# BMS_Schematic.net
KiCad netlist of a schematic drawn in EAGLE
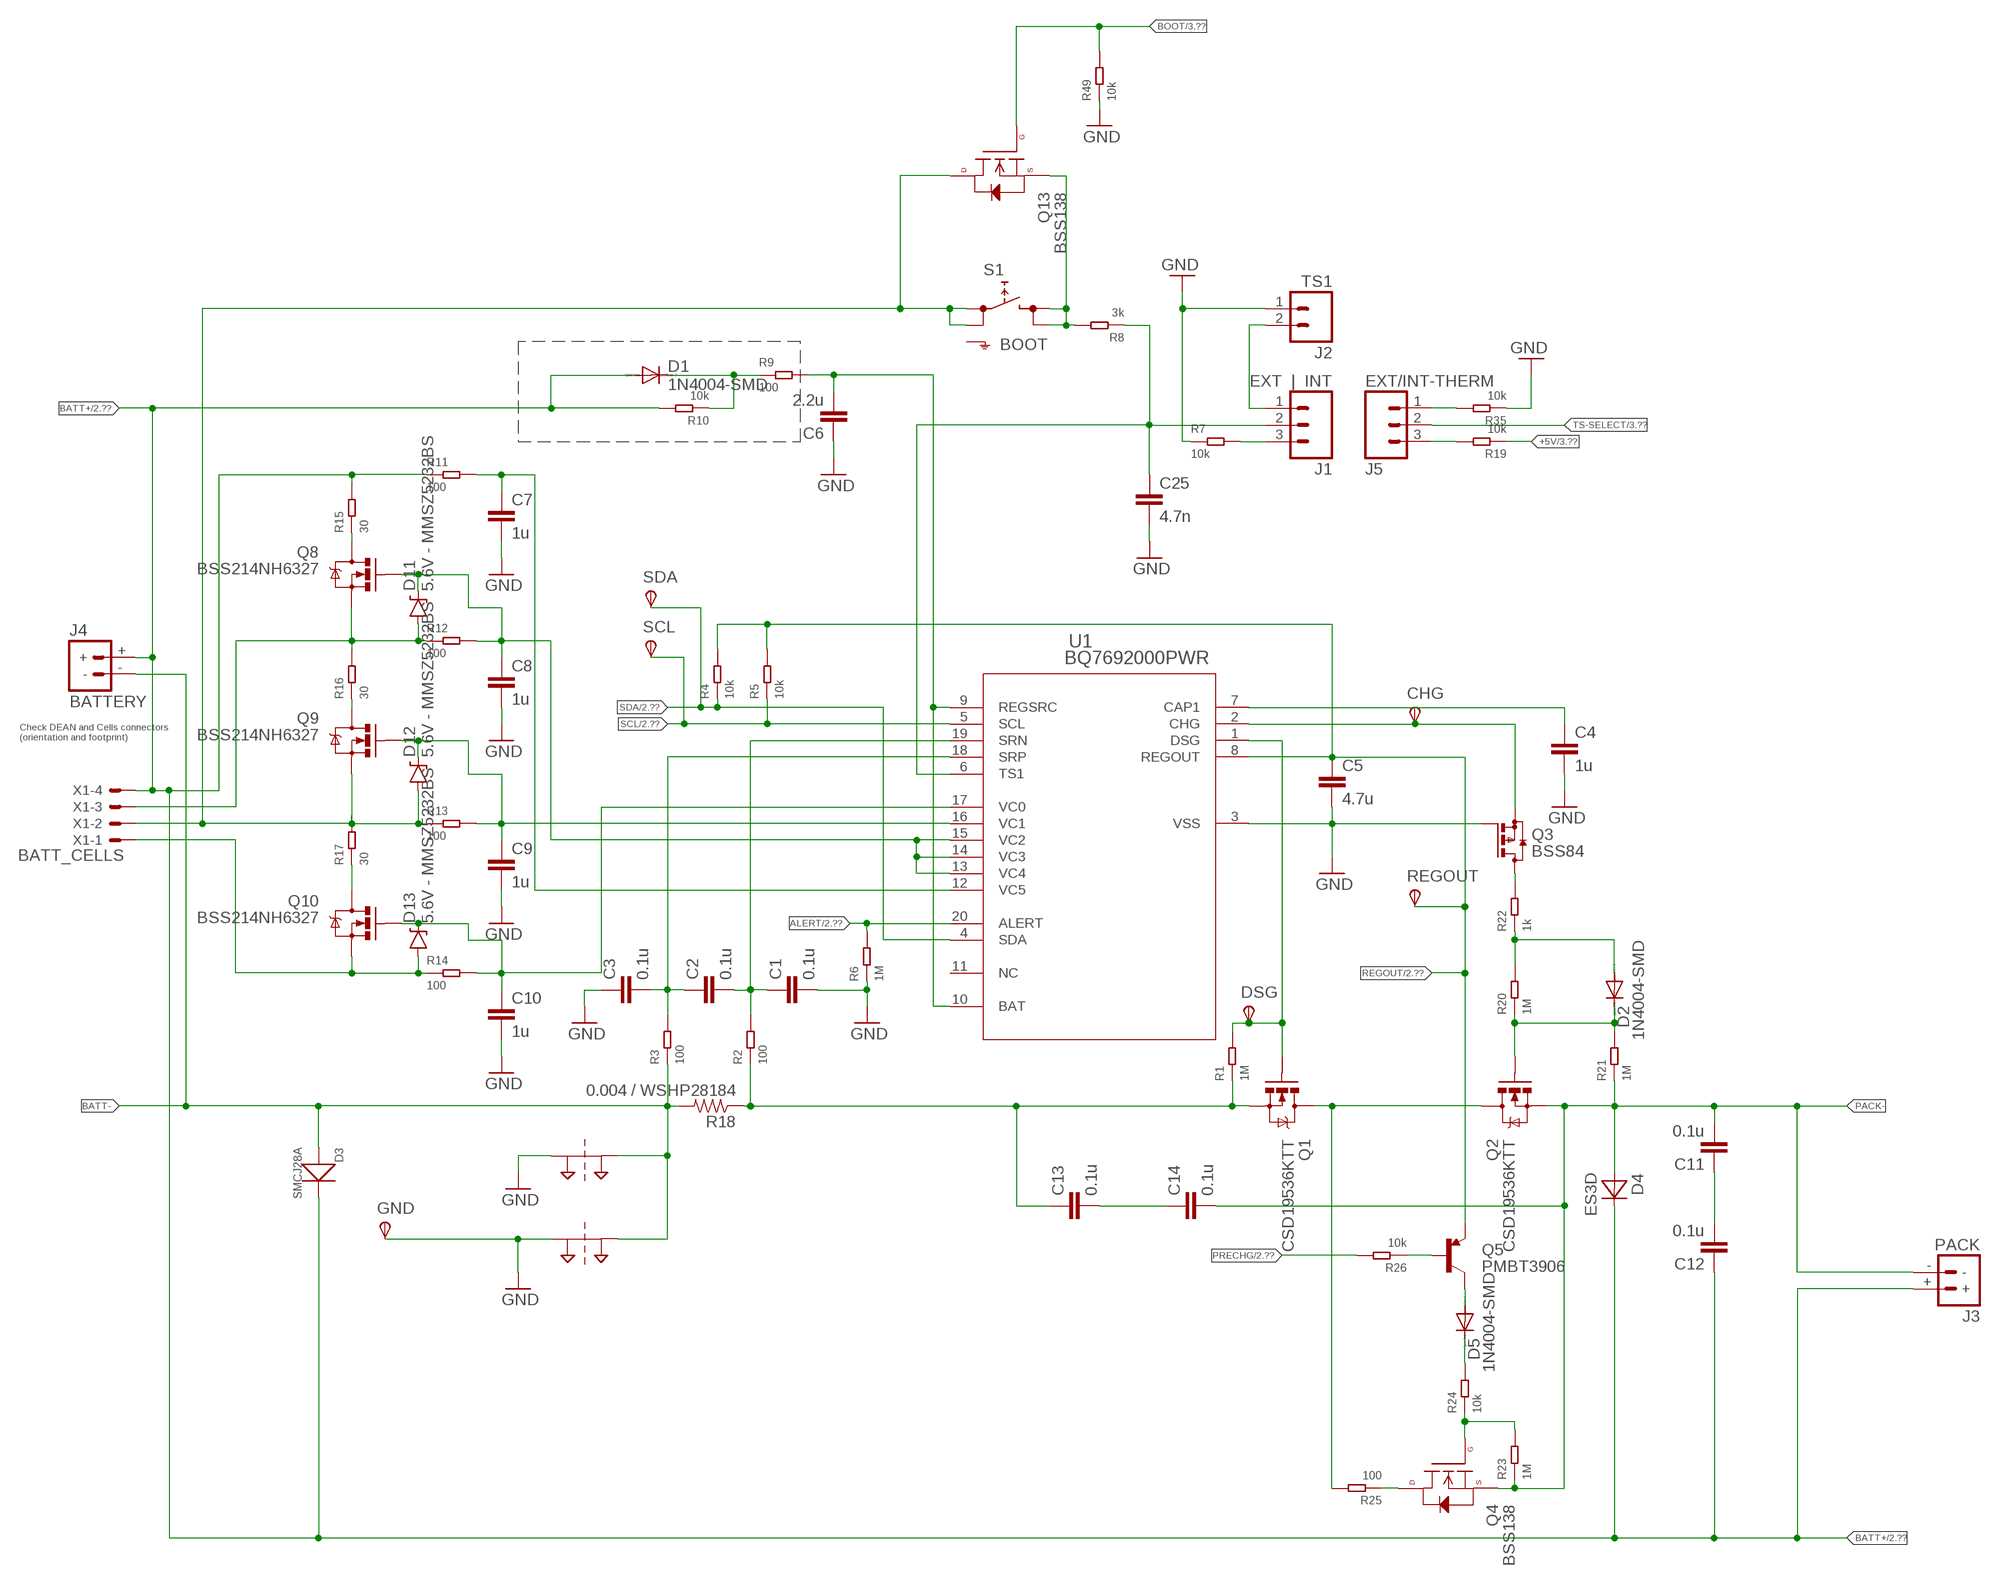
[diagram p0: schematic, sheet 1]
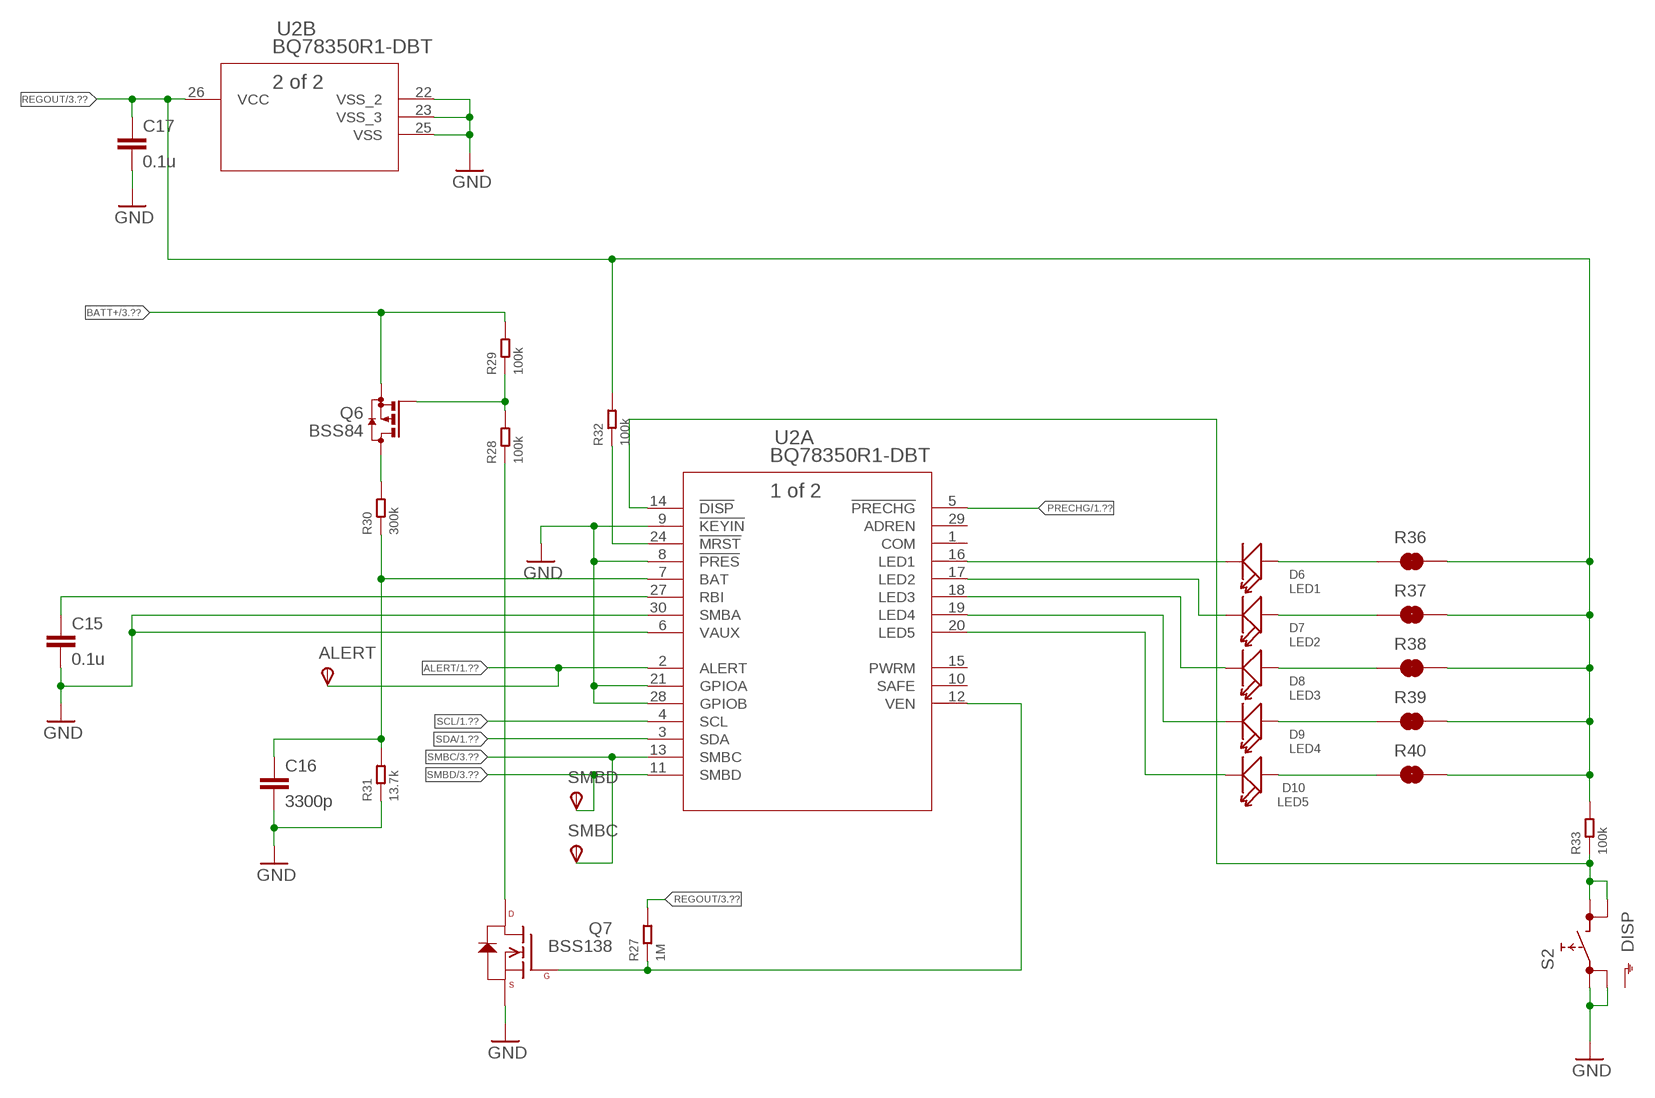
[diagram p1: schematic, sheet 2]
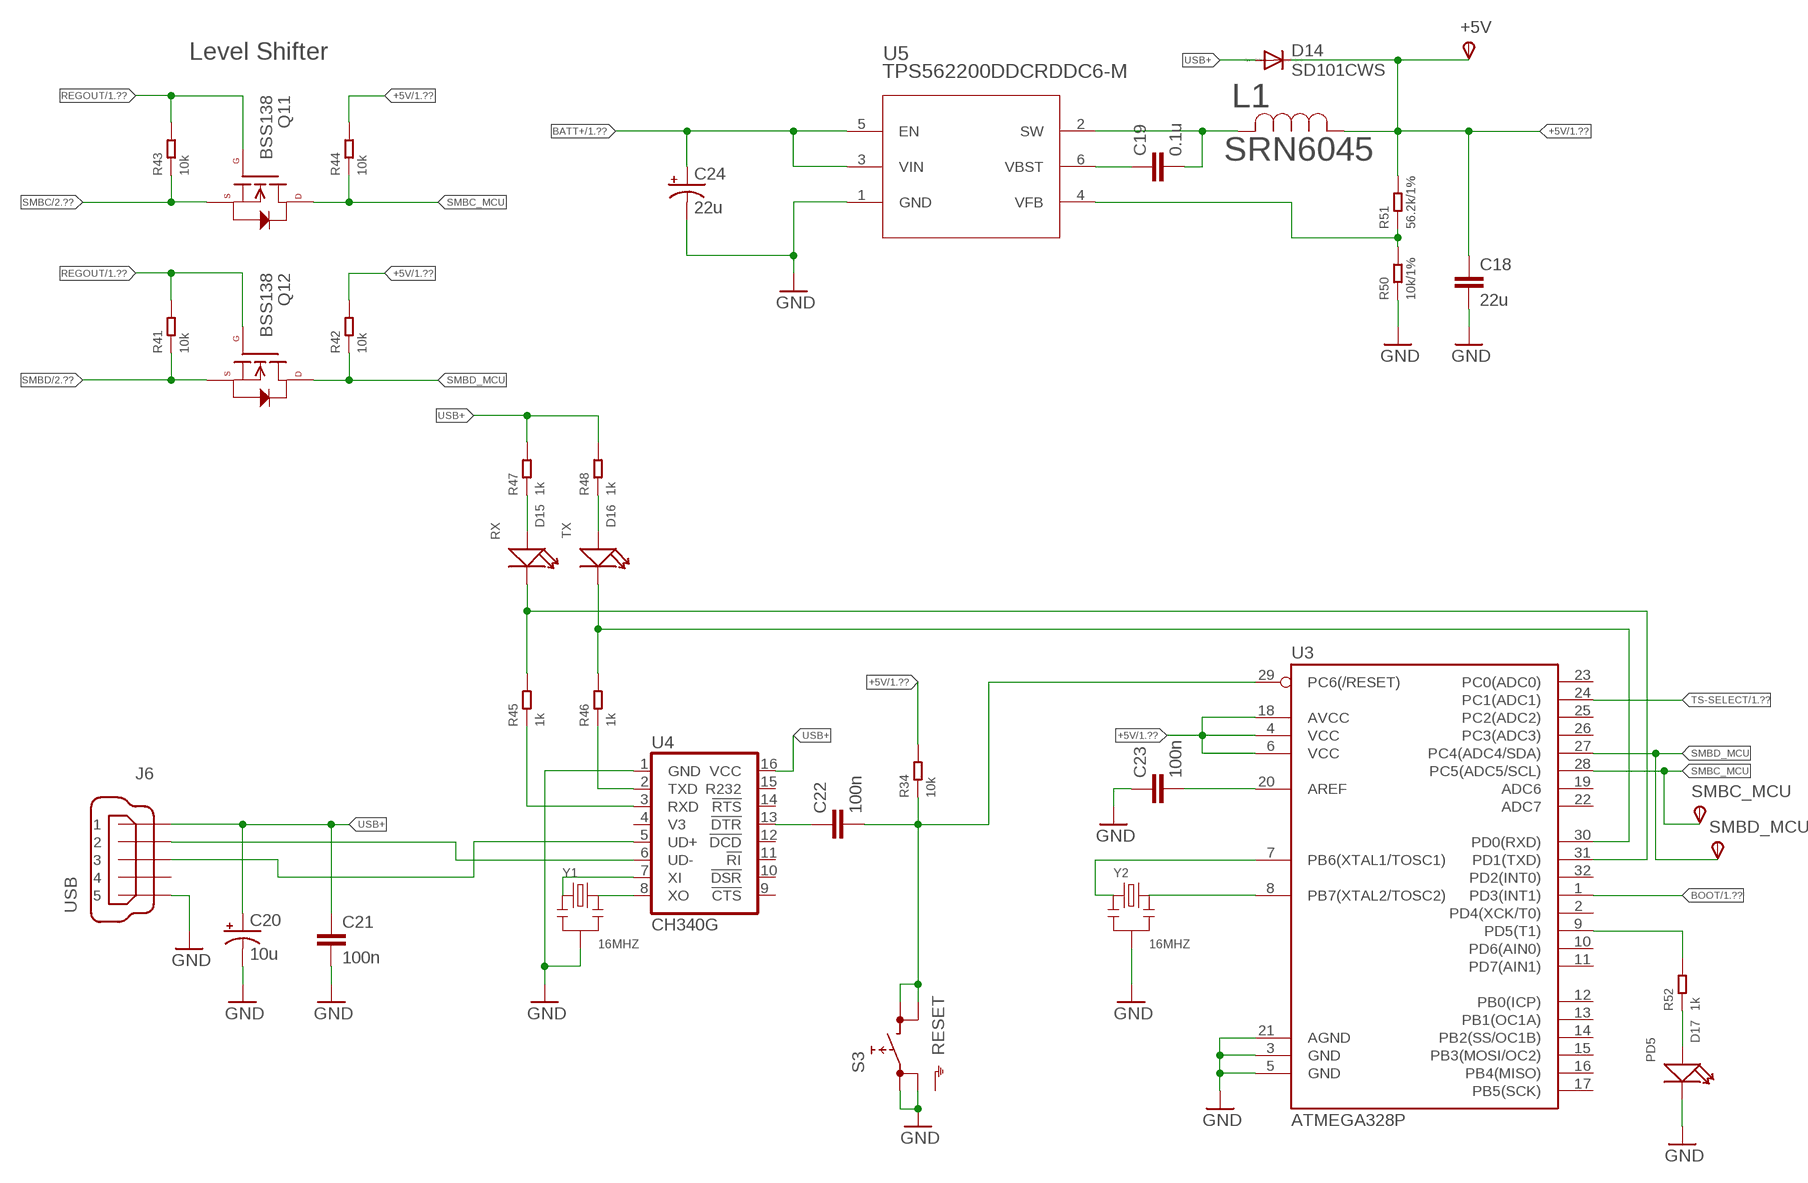
[diagram p2: schematic, sheet 3]

(export (version "E")
  (design (tool "Eeschema 10.0.6"))
  (components
    (comp (ref "C1")
      (value "0.1u")
      (footprint "eagle-import:0805")
      (libsource (lib "eagle-import") (part "CAP0805"))
    )
    (comp (ref "C2")
      (value "0.1u")
      (footprint "eagle-import:0805")
      (libsource (lib "eagle-import") (part "CAP0805"))
    )
    (comp (ref "C3")
      (value "0.1u")
      (footprint "eagle-import:0805")
      (libsource (lib "eagle-import") (part "CAP0805"))
    )
    (comp (ref "C4")
      (value "1u")
      (footprint "eagle-import:0805")
      (libsource (lib "eagle-import") (part "CAP0805"))
    )
    (comp (ref "C5")
      (value "4.7u")
      (footprint "eagle-import:0805")
      (libsource (lib "eagle-import") (part "CAP0805"))
    )
    (comp (ref "C6")
      (value "2.2u")
      (footprint "eagle-import:C1206")
      (libsource (lib "eagle-import") (part "C-EUC1206"))
    )
    (comp (ref "C7")
      (value "1u")
      (footprint "eagle-import:0805")
      (libsource (lib "eagle-import") (part "CAP0805"))
    )
    (comp (ref "C8")
      (value "1u")
      (footprint "eagle-import:0805")
      (libsource (lib "eagle-import") (part "CAP0805"))
    )
    (comp (ref "C9")
      (value "1u")
      (footprint "eagle-import:0805")
      (libsource (lib "eagle-import") (part "CAP0805"))
    )
    (comp (ref "C10")
      (value "1u")
      (footprint "eagle-import:0805")
      (libsource (lib "eagle-import") (part "CAP0805"))
    )
    (comp (ref "C11")
      (value "0.1u")
      (footprint "eagle-import:0805")
      (libsource (lib "eagle-import") (part "CAP0805"))
    )
    (comp (ref "C12")
      (value "0.1u")
      (footprint "eagle-import:0805")
      (libsource (lib "eagle-import") (part "CAP0805"))
    )
    (comp (ref "C13")
      (value "0.1u")
      (footprint "eagle-import:0805")
      (libsource (lib "eagle-import") (part "CAP0805"))
    )
    (comp (ref "C14")
      (value "0.1u")
      (footprint "eagle-import:0805")
      (libsource (lib "eagle-import") (part "CAP0805"))
    )
    (comp (ref "C25")
      (value "4.7n")
      (footprint "eagle-import:0805")
      (libsource (lib "eagle-import") (part "CAP0805"))
    )
    (comp (ref "CHG")
      (value "TPSB2,54")
      (footprint "eagle-import:B2,54")
      (libsource (lib "eagle-import") (part "TPSB2,54"))
    )
    (comp (ref "D1")
      (value "1N4004-SMD")
      (footprint "eagle-import:DO-214")
      (libsource (lib "eagle-import") (part "1N4004-SMD"))
    )
    (comp (ref "D2")
      (value "1N4004-SMD")
      (footprint "eagle-import:DO-214")
      (libsource (lib "eagle-import") (part "1N4004-SMD"))
    )
    (comp (ref "D3")
      (value "SMCJ28A")
      (footprint "eagle-import:DO-214AB")
      (fields (field (name "MPN") "SS34-E3/57T"))
      (libsource (lib "eagle-import") (part "SMD-DIODE-SCHOTTKY-40V-3A(DO-214AB)"))
    )
    (comp (ref "D4")
      (value "ES3D")
      (footprint "eagle-import:SMC")
      (libsource (lib "eagle-import") (part "ES3D"))
    )
    (comp (ref "D5")
      (value "1N4004-SMD")
      (footprint "eagle-import:DO-214")
      (libsource (lib "eagle-import") (part "1N4004-SMD"))
    )
    (comp (ref "D11")
      (value "5.6V - MMSZ5232BS")
      (footprint "eagle-import:SOD-323")
      (libsource (lib "eagle-import") (part "DIODE-ZENER5.6V"))
    )
    (comp (ref "D12")
      (value "5.6V - MMSZ5232BS")
      (footprint "eagle-import:SOD-323")
      (libsource (lib "eagle-import") (part "DIODE-ZENER5.6V"))
    )
    (comp (ref "D13")
      (value "5.6V - MMSZ5232BS")
      (footprint "eagle-import:SOD-323")
      (libsource (lib "eagle-import") (part "DIODE-ZENER5.6V"))
    )
    (comp (ref "DSG")
      (value "TPSB2,54")
      (footprint "eagle-import:B2,54")
      (libsource (lib "eagle-import") (part "TPSB2,54"))
    )
    (comp (ref "GND")
      (value "GND")
      (footprint "eagle-import:P1-17")
      (fields (field (name "SPICEPREFIX") "X"))
      (libsource (lib "eagle-import") (part "TPSPAD1-17"))
    )
    (comp (ref "J1")
      (value "EXT | INT")
      (footprint "eagle-import:1X03")
      (libsource (lib "eagle-import") (part "M03PTH"))
    )
    (comp (ref "J2")
      (value "TS1")
      (footprint "eagle-import:1X02")
      (libsource (lib "eagle-import") (part "M02PTH"))
    )
    (comp (ref "J3")
      (value "PACK")
      (footprint "eagle-import:DEANS")
      (libsource (lib "eagle-import") (part "BATTERY_CONNDEANS"))
    )
    (comp (ref "J4")
      (value "BATTERY")
      (footprint "eagle-import:DEANS")
      (libsource (lib "eagle-import") (part "BATTERY_CONNDEANS"))
    )
    (comp (ref "J5")
      (value "EXT/INT-THERM")
      (footprint "eagle-import:1X03")
      (libsource (lib "eagle-import") (part "M03PTH"))
    )
    (comp (ref "PT1")
      (value "2PT_GND_TIE")
      (footprint "eagle-import:2PT_GND_TIE")
      (libsource (lib "eagle-import") (part "2PT_GND_TIE"))
    )
    (comp (ref "PT2")
      (value "2PT_GND_TIE")
      (footprint "eagle-import:2PT_GND_TIE")
      (libsource (lib "eagle-import") (part "2PT_GND_TIE"))
    )
    (comp (ref "Q1")
      (value "CSD19536KTT")
      (footprint "eagle-import:TO-263_D2PAK")
      (libsource (lib "eagle-import") (part "MOSFET-NCHANNELPSMN7R0"))
    )
    (comp (ref "Q2")
      (value "CSD19536KTT")
      (footprint "eagle-import:TO-263_D2PAK")
      (libsource (lib "eagle-import") (part "MOSFET-NCHANNELPSMN7R0"))
    )
    (comp (ref "Q3")
      (value "BSS84")
      (footprint "eagle-import:SOT23")
      (libsource (lib "eagle-import") (part "BSS84"))
    )
    (comp (ref "Q4")
      (value "BSS138")
      (footprint "eagle-import:SOT23-3")
      (libsource (lib "eagle-import") (part "N-CHANNEL-MOSFET-BSS138"))
    )
    (comp (ref "Q5")
      (value "PMBT3906")
      (footprint "eagle-import:SOT23-3")
      (libsource (lib "eagle-import") (part "TRANSISTOR_PNPPMBT3906"))
    )
    (comp (ref "Q8")
      (value "BSS214NH6327")
      (footprint "eagle-import:SOT23-3")
      (libsource (lib "eagle-import") (part "MOSFET-NCHANNELBSS138"))
    )
    (comp (ref "Q9")
      (value "BSS214NH6327")
      (footprint "eagle-import:SOT23-3")
      (libsource (lib "eagle-import") (part "MOSFET-NCHANNELBSS138"))
    )
    (comp (ref "Q10")
      (value "BSS214NH6327")
      (footprint "eagle-import:SOT23-3")
      (libsource (lib "eagle-import") (part "MOSFET-NCHANNELBSS138"))
    )
    (comp (ref "Q13")
      (value "BSS138")
      (footprint "eagle-import:SOT23-3")
      (libsource (lib "eagle-import") (part "N-CHANNEL-MOSFET-BSS138"))
    )
    (comp (ref "R1")
      (value "1M")
      (footprint "eagle-import:R0805")
      (libsource (lib "eagle-import") (part "RES-0805"))
    )
    (comp (ref "R2")
      (value "100")
      (footprint "eagle-import:R0805")
      (libsource (lib "eagle-import") (part "RES-0805"))
    )
    (comp (ref "R3")
      (value "100")
      (footprint "eagle-import:R0805")
      (libsource (lib "eagle-import") (part "RES-0805"))
    )
    (comp (ref "R4")
      (value "10k")
      (footprint "eagle-import:R0805")
      (libsource (lib "eagle-import") (part "RES-0805"))
    )
    (comp (ref "R5")
      (value "10k")
      (footprint "eagle-import:R0805")
      (libsource (lib "eagle-import") (part "RES-0805"))
    )
    (comp (ref "R6")
      (value "1M")
      (footprint "eagle-import:R0805")
      (libsource (lib "eagle-import") (part "RES-0805"))
    )
    (comp (ref "R7")
      (value "10k")
      (footprint "eagle-import:R0805")
      (libsource (lib "eagle-import") (part "RES-0805"))
    )
    (comp (ref "R8")
      (value "3k")
      (footprint "eagle-import:R0805")
      (libsource (lib "eagle-import") (part "RES-0805"))
    )
    (comp (ref "R9")
      (value "100")
      (footprint "eagle-import:R0805")
      (libsource (lib "eagle-import") (part "RES-0805"))
    )
    (comp (ref "R10")
      (value "10k")
      (footprint "eagle-import:R0805")
      (libsource (lib "eagle-import") (part "RES-0805"))
    )
    (comp (ref "R11")
      (value "100")
      (footprint "eagle-import:R0805")
      (libsource (lib "eagle-import") (part "RES-0805"))
    )
    (comp (ref "R12")
      (value "100")
      (footprint "eagle-import:R0805")
      (libsource (lib "eagle-import") (part "RES-0805"))
    )
    (comp (ref "R13")
      (value "100")
      (footprint "eagle-import:R0805")
      (libsource (lib "eagle-import") (part "RES-0805"))
    )
    (comp (ref "R14")
      (value "100")
      (footprint "eagle-import:R0805")
      (libsource (lib "eagle-import") (part "RES-0805"))
    )
    (comp (ref "R15")
      (value "30")
      (footprint "eagle-import:R2512")
      (libsource (lib "eagle-import") (part "RES-2512"))
    )
    (comp (ref "R16")
      (value "30")
      (footprint "eagle-import:R2512")
      (libsource (lib "eagle-import") (part "RES-2512"))
    )
    (comp (ref "R17")
      (value "30")
      (footprint "eagle-import:R2512")
      (libsource (lib "eagle-import") (part "RES-2512"))
    )
    (comp (ref "R18")
      (value "0.004 / WSHP28184")
      (footprint "eagle-import:2512")
      (libsource (lib "eagle-import") (part "0.001OHM-3W-1%(2512)3W/1%"))
    )
    (comp (ref "R19")
      (value "10k")
      (footprint "eagle-import:R0805")
      (libsource (lib "eagle-import") (part "RES-0805"))
    )
    (comp (ref "R20")
      (value "1M")
      (footprint "eagle-import:R0805")
      (libsource (lib "eagle-import") (part "RES-0805"))
    )
    (comp (ref "R21")
      (value "1M")
      (footprint "eagle-import:R0805")
      (libsource (lib "eagle-import") (part "RES-0805"))
    )
    (comp (ref "R22")
      (value "1k")
      (footprint "eagle-import:R0805")
      (libsource (lib "eagle-import") (part "RES-0805"))
    )
    (comp (ref "R23")
      (value "1M")
      (footprint "eagle-import:R0805")
      (libsource (lib "eagle-import") (part "RES-0805"))
    )
    (comp (ref "R24")
      (value "10k")
      (footprint "eagle-import:R0805")
      (libsource (lib "eagle-import") (part "RES-0805"))
    )
    (comp (ref "R25")
      (value "100")
      (footprint "eagle-import:R2512")
      (libsource (lib "eagle-import") (part "RES-2512"))
    )
    (comp (ref "R26")
      (value "10k")
      (footprint "eagle-import:R0805")
      (libsource (lib "eagle-import") (part "RES-0805"))
    )
    (comp (ref "R35")
      (value "10k")
      (footprint "eagle-import:R0805")
      (libsource (lib "eagle-import") (part "RES-0805"))
    )
    (comp (ref "R49")
      (value "10k")
      (footprint "eagle-import:R0805")
      (libsource (lib "eagle-import") (part "RES-0805"))
    )
    (comp (ref "REGOUT")
      (value "TPSB2,54")
      (footprint "eagle-import:B2,54")
      (libsource (lib "eagle-import") (part "TPSB2,54"))
    )
    (comp (ref "S1")
      (value "BOOT")
      (footprint "eagle-import:SKHMPXE010")
      (libsource (lib "eagle-import") (part "SKHMPE010S"))
    )
    (comp (ref "SCL")
      (value "TPSB2,54")
      (footprint "eagle-import:B2,54")
      (libsource (lib "eagle-import") (part "TPSB2,54"))
    )
    (comp (ref "SDA")
      (value "TPSB2,54")
      (footprint "eagle-import:B2,54")
      (libsource (lib "eagle-import") (part "TPSB2,54"))
    )
    (comp (ref "U1")
      (value "BQ7692000PWR")
      (footprint "eagle-import:PW20")
      (fields (field (name "MANUFACTURER_PART_NUMBER") "BQ7692006PWR"))
      (libsource (lib "eagle-import") (part "BQ7692006PWR"))
    )
    (comp (ref "X1")
      (value "BATT_CELLS")
      (footprint "eagle-import:70543-04")
      (libsource (lib "eagle-import") (part "C-GRID-04-70543"))
    )
    (comp (ref "ALERT")
      (value "TPSB2,54")
      (footprint "eagle-import:B2,54")
      (libsource (lib "eagle-import") (part "TPSB2,54"))
    )
    (comp (ref "C15")
      (value "0.1u")
      (footprint "eagle-import:0805")
      (libsource (lib "eagle-import") (part "CAP0805"))
    )
    (comp (ref "C16")
      (value "3300p")
      (footprint "eagle-import:0805")
      (libsource (lib "eagle-import") (part "CAP0805"))
    )
    (comp (ref "C17")
      (value "0.1u")
      (footprint "eagle-import:0805")
      (libsource (lib "eagle-import") (part "CAP0805"))
    )
    (comp (ref "D6")
      (value "LED1")
      (footprint "eagle-import:LED-0805")
      (fields (field (name "MPN") "17-215SYGC/S530-E2/TR8"))
      (libsource (lib "eagle-import") (part "SMD-LED-CLEAR-GREEN(0805)"))
    )
    (comp (ref "D7")
      (value "LED2")
      (footprint "eagle-import:LED-0805")
      (fields (field (name "MPN") "17-215SYGC/S530-E2/TR8"))
      (libsource (lib "eagle-import") (part "SMD-LED-CLEAR-GREEN(0805)"))
    )
    (comp (ref "D8")
      (value "LED3")
      (footprint "eagle-import:LED-0805")
      (fields (field (name "MPN") "17-215SYGC/S530-E2/TR8"))
      (libsource (lib "eagle-import") (part "SMD-LED-CLEAR-GREEN(0805)"))
    )
    (comp (ref "D9")
      (value "LED4")
      (footprint "eagle-import:LED-0805")
      (fields (field (name "MPN") "17-215SYGC/S530-E2/TR8"))
      (libsource (lib "eagle-import") (part "SMD-LED-CLEAR-GREEN(0805)"))
    )
    (comp (ref "D10")
      (value "LED5")
      (footprint "eagle-import:LED-0805")
      (fields (field (name "MPN") "17-215SURC/S530-A2/TR8"))
      (libsource (lib "eagle-import") (part "SMD-LED-CLEAR-RED(0805)"))
    )
    (comp (ref "Q6")
      (value "BSS84")
      (footprint "eagle-import:SOT23")
      (libsource (lib "eagle-import") (part "BSS84"))
    )
    (comp (ref "Q7")
      (value "BSS138")
      (footprint "eagle-import:SOT23-3")
      (libsource (lib "eagle-import") (part "N-CHANNEL-MOSFET-BSS138"))
    )
    (comp (ref "R27")
      (value "1M")
      (footprint "eagle-import:R0805")
      (libsource (lib "eagle-import") (part "RES-0805"))
    )
    (comp (ref "R28")
      (value "100k")
      (footprint "eagle-import:R0805")
      (libsource (lib "eagle-import") (part "RES-0805"))
    )
    (comp (ref "R29")
      (value "100k")
      (footprint "eagle-import:R0805")
      (libsource (lib "eagle-import") (part "RES-0805"))
    )
    (comp (ref "R30")
      (value "300k")
      (footprint "eagle-import:R0805")
      (libsource (lib "eagle-import") (part "RES-0805"))
    )
    (comp (ref "R31")
      (value "13.7k")
      (footprint "eagle-import:R0805")
      (libsource (lib "eagle-import") (part "RES-0805"))
    )
    (comp (ref "R32")
      (value "100k")
      (footprint "eagle-import:R0805")
      (libsource (lib "eagle-import") (part "RES-0805"))
    )
    (comp (ref "R33")
      (value "100k")
      (footprint "eagle-import:R0805")
      (libsource (lib "eagle-import") (part "RES-0805"))
    )
    (comp (ref "R36")
      (value "JUMPER-NC-0805")
      (footprint "eagle-import:R0805")
      (libsource (lib "eagle-import") (part "JUMPER-NC-0805"))
    )
    (comp (ref "R37")
      (value "JUMPER-NC-0805")
      (footprint "eagle-import:R0805")
      (libsource (lib "eagle-import") (part "JUMPER-NC-0805"))
    )
    (comp (ref "R38")
      (value "JUMPER-NC-0805")
      (footprint "eagle-import:R0805")
      (libsource (lib "eagle-import") (part "JUMPER-NC-0805"))
    )
    (comp (ref "R39")
      (value "JUMPER-NC-0805")
      (footprint "eagle-import:R0805")
      (libsource (lib "eagle-import") (part "JUMPER-NC-0805"))
    )
    (comp (ref "R40")
      (value "JUMPER-NC-0805")
      (footprint "eagle-import:R0805")
      (libsource (lib "eagle-import") (part "JUMPER-NC-0805"))
    )
    (comp (ref "S2")
      (value "DISP")
      (footprint "eagle-import:SKHMPXE010")
      (libsource (lib "eagle-import") (part "SKHMPE010S"))
    )
    (comp (ref "SMBC")
      (value "TPSB2,54")
      (footprint "eagle-import:B2,54")
      (libsource (lib "eagle-import") (part "TPSB2,54"))
    )
    (comp (ref "SMBD")
      (value "TPSB2,54")
      (footprint "eagle-import:B2,54")
      (libsource (lib "eagle-import") (part "TPSB2,54"))
    )
    (comp (ref "U2")
      (value "BQ78350R1-DBT")
      (footprint "eagle-import:DBT30")
      (fields (field (name "MANUFACTURER_PART_NUMBER") "BQ78350DBT"))
      (libsource (lib "eagle-import") (part "BQ78350R1-DBT"))
    )
    (comp (ref "+5V")
      (value "TPSB2,54")
      (footprint "eagle-import:B2,54")
      (libsource (lib "eagle-import") (part "TPSB2,54"))
    )
    (comp (ref "C18")
      (value "22u")
      (footprint "eagle-import:0805")
      (libsource (lib "eagle-import") (part "CAP0805"))
    )
    (comp (ref "C19")
      (value "0.1u")
      (footprint "eagle-import:0805")
      (libsource (lib "eagle-import") (part "CAP0805"))
    )
    (comp (ref "C20")
      (value "10u")
      (footprint "eagle-import:EIA3216-KIT")
      (libsource (lib "eagle-import") (part "CAP_POL1206-KIT"))
    )
    (comp (ref "C21")
      (value "100n")
      (footprint "eagle-import:0603-CAP")
      (libsource (lib "eagle-import") (part "CAP0603-CAP"))
    )
    (comp (ref "C22")
      (value "100n")
      (footprint "eagle-import:0603-CAP")
      (libsource (lib "eagle-import") (part "CAP0603-CAP"))
    )
    (comp (ref "C23")
      (value "100n")
      (footprint "eagle-import:0603-CAP")
      (libsource (lib "eagle-import") (part "CAP0603-CAP"))
    )
    (comp (ref "C24")
      (value "22u")
      (footprint "eagle-import:PANASONIC_C")
      (libsource (lib "eagle-import") (part "CAP_POLC"))
    )
    (comp (ref "D14")
      (value "SD101CWS")
      (footprint "eagle-import:SOD323-W")
      (libsource (lib "eagle-import") (part "DIODE-SOD323-W"))
    )
    (comp (ref "D15")
      (value "RX")
      (footprint "eagle-import:LED-0805")
      (fields (field (name "MPN") "17-215SYGC/S530-E2/TR8"))
      (libsource (lib "eagle-import") (part "SMD-LED-CLEAR-GREEN(0805)"))
    )
    (comp (ref "D16")
      (value "TX")
      (footprint "eagle-import:LED-0805")
      (fields (field (name "MPN") "17-215SYGC/S530-E2/TR8"))
      (libsource (lib "eagle-import") (part "SMD-LED-CLEAR-GREEN(0805)"))
    )
    (comp (ref "D17")
      (value "PD5")
      (footprint "eagle-import:LED-0805")
      (fields (field (name "MPN") "17-215SYGC/S530-E2/TR8"))
      (libsource (lib "eagle-import") (part "SMD-LED-CLEAR-GREEN(0805)"))
    )
    (comp (ref "J6")
      (value "USB")
      (footprint "eagle-import:USB-MINI-B_2")
      (libsource (lib "eagle-import") (part "MINI-USB-ARDUINO-NANO"))
    )
    (comp (ref "L1")
      (value "SRN6045")
      (footprint "eagle-import:IND_BOURNS_SRN6045")
      (libsource (lib "eagle-import") (part "BOURNS_SRN6045"))
    )
    (comp (ref "Q11")
      (value "BSS138")
      (footprint "eagle-import:SOT23-3")
      (libsource (lib "eagle-import") (part "N-CHANNEL-MOSFET-BSS138"))
    )
    (comp (ref "Q12")
      (value "BSS138")
      (footprint "eagle-import:SOT23-3")
      (libsource (lib "eagle-import") (part "N-CHANNEL-MOSFET-BSS138"))
    )
    (comp (ref "R34")
      (value "10k")
      (footprint "eagle-import:R0805")
      (libsource (lib "eagle-import") (part "RES-0805"))
    )
    (comp (ref "R41")
      (value "10k")
      (footprint "eagle-import:R0805")
      (libsource (lib "eagle-import") (part "RES-0805"))
    )
    (comp (ref "R42")
      (value "10k")
      (footprint "eagle-import:R0805")
      (libsource (lib "eagle-import") (part "RES-0805"))
    )
    (comp (ref "R43")
      (value "10k")
      (footprint "eagle-import:R0805")
      (libsource (lib "eagle-import") (part "RES-0805"))
    )
    (comp (ref "R44")
      (value "10k")
      (footprint "eagle-import:R0805")
      (libsource (lib "eagle-import") (part "RES-0805"))
    )
    (comp (ref "R45")
      (value "1k")
      (footprint "eagle-import:R0805")
      (libsource (lib "eagle-import") (part "RES-0805"))
    )
    (comp (ref "R46")
      (value "1k")
      (footprint "eagle-import:R0805")
      (libsource (lib "eagle-import") (part "RES-0805"))
    )
    (comp (ref "R47")
      (value "1k")
      (footprint "eagle-import:R0805")
      (libsource (lib "eagle-import") (part "RES-0805"))
    )
    (comp (ref "R48")
      (value "1k")
      (footprint "eagle-import:R0805")
      (libsource (lib "eagle-import") (part "RES-0805"))
    )
    (comp (ref "R50")
      (value "10k/1%")
      (footprint "eagle-import:R0805")
      (libsource (lib "eagle-import") (part "RES-0805"))
    )
    (comp (ref "R51")
      (value "56.2k/1%")
      (footprint "eagle-import:R0805")
      (libsource (lib "eagle-import") (part "RES-0805"))
    )
    (comp (ref "R52")
      (value "1k")
      (footprint "eagle-import:R0805")
      (libsource (lib "eagle-import") (part "RES-0805"))
    )
    (comp (ref "S3")
      (value "RESET")
      (footprint "eagle-import:SKHMPXE010")
      (libsource (lib "eagle-import") (part "SKHMPE010S"))
    )
    (comp (ref "SMBC_MCU")
      (value "TPSB2,54")
      (footprint "eagle-import:B2,54")
      (libsource (lib "eagle-import") (part "TPSB2,54"))
    )
    (comp (ref "SMBD_MCU")
      (value "TPSB2,54")
      (footprint "eagle-import:B2,54")
      (libsource (lib "eagle-import") (part "TPSB2,54"))
    )
    (comp (ref "U3")
      (value "ATMEGA328P")
      (footprint "eagle-import:TQFP32-08")
      (libsource (lib "eagle-import") (part "ATMEGA328P_TQFP"))
    )
    (comp (ref "U4")
      (value "CH340G")
      (footprint "eagle-import:SO016")
      (libsource (lib "eagle-import") (part "CH340GSMD"))
    )
    (comp (ref "U5")
      (value "TPS562200DDCRDDC6-M")
      (footprint "eagle-import:DDC6-M")
      (fields (field (name "MANUFACTURER_PART_NUMBER") "TPS562200DDCR"))
      (libsource (lib "eagle-import") (part "TPS562200DDCRDDC6-M"))
    )
    (comp (ref "Y1")
      (value "16MHZ")
      (footprint "eagle-import:X3-SMD-3.6X1.3X0.8MM")
      (fields (field (name "MPN") "CSTCE16M0V53-R0"))
      (libsource (lib "eagle-import") (part "SMD-RESONATOR-16MHZ-15PF-0.5%-40R(3P-3.2X1.3MM)"))
    )
    (comp (ref "Y2")
      (value "16MHZ")
      (footprint "eagle-import:X3-SMD-3.6X1.3X0.8MM")
      (fields (field (name "MPN") "CSTCE16M0V53-R0"))
      (libsource (lib "eagle-import") (part "SMD-RESONATOR-16MHZ-15PF-0.5%-40R(3P-3.2X1.3MM)"))
    )
  )
  (nets
    (net (code "1") (name "+5V") (class "Default")
      (node (ref "+5V") (pin "TP") (pinfunction "PP_TP") (pintype "input"))
      (node (ref "C18") (pin "1") (pinfunction "1_1") (pintype "passive"))
      (node (ref "D14") (pin "C") (pinfunction "C_C") (pintype "passive"))
      (node (ref "L1") (pin "1") (pinfunction "1_1") (pintype "passive"))
      (node (ref "R19") (pin "1") (pinfunction "1_1") (pintype "passive"))
      (node (ref "R34") (pin "2") (pinfunction "2_2") (pintype "passive"))
      (node (ref "R42") (pin "2") (pinfunction "2_2") (pintype "passive"))
      (node (ref "R44") (pin "2") (pinfunction "2_2") (pintype "passive"))
      (node (ref "R51") (pin "2") (pinfunction "2_2") (pintype "passive"))
      (node (ref "U3") (pin "18") (pinfunction "AVCC_18") (pintype "bidirectional"))
      (node (ref "U3") (pin "4") (pinfunction "VCC_4") (pintype "bidirectional"))
      (node (ref "U3") (pin "6") (pinfunction "VCC_6") (pintype "bidirectional"))
    )
    (net (code "2") (name "ALERT") (class "Default")
      (node (ref "ALERT") (pin "TP") (pinfunction "PP_TP") (pintype "input"))
      (node (ref "R6") (pin "2") (pinfunction "2_2") (pintype "passive"))
      (node (ref "U1") (pin "20") (pinfunction "ALERT_20") (pintype "bidirectional"))
      (node (ref "U2") (pin "2") (pinfunction "ALERT_2") (pintype "bidirectional"))
    )
    (net (code "3") (name "BATT+") (class "Default")
      (node (ref "C12") (pin "1") (pinfunction "1_1") (pintype "passive"))
      (node (ref "C24") (pin "+") (pinfunction "+_+") (pintype "passive"))
      (node (ref "D1") (pin "A") (pinfunction "A_A") (pintype "passive"))
      (node (ref "D3") (pin "2") (pinfunction "-_2") (pintype "passive"))
      (node (ref "D4") (pin "C") (pinfunction "C_C") (pintype "passive"))
      (node (ref "J3") (pin "+") (pinfunction "+_+") (pintype "passive"))
      (node (ref "J4") (pin "+") (pinfunction "+_+") (pintype "passive"))
      (node (ref "Q6") (pin "2") (pinfunction "S_2") (pintype "passive"))
      (node (ref "R10") (pin "2") (pinfunction "2_2") (pintype "passive"))
      (node (ref "R11") (pin "1") (pinfunction "1_1") (pintype "passive"))
      (node (ref "R15") (pin "2") (pinfunction "2_2") (pintype "passive"))
      (node (ref "R29") (pin "2") (pinfunction "2_2") (pintype "passive"))
      (node (ref "U5") (pin "3") (pinfunction "VIN_3") (pintype "input"))
      (node (ref "U5") (pin "5") (pinfunction "EN_5") (pintype "input"))
      (node (ref "X1") (pin "4") (pinfunction "S_4") (pintype "passive"))
    )
    (net (code "4") (name "BATT-") (class "Default")
      (node (ref "D3") (pin "1") (pinfunction "+_1") (pintype "passive"))
      (node (ref "J4") (pin "-") (pinfunction "-_-") (pintype "passive"))
      (node (ref "PT1") (pin "P$2") (pinfunction "P$2_P$2") (pintype "bidirectional"))
      (node (ref "PT2") (pin "P$2") (pinfunction "P$2_P$2") (pintype "bidirectional"))
      (node (ref "R18") (pin "2") (pinfunction "2_2") (pintype "passive"))
      (node (ref "R3") (pin "1") (pinfunction "1_1") (pintype "passive"))
    )
    (net (code "5") (name "BOOT") (class "Default")
      (node (ref "Q13") (pin "1") (pinfunction "G_1") (pintype "passive"))
      (node (ref "R49") (pin "2") (pinfunction "2_2") (pintype "passive"))
      (node (ref "U3") (pin "1") (pinfunction "PD3(INT1)_1") (pintype "bidirectional"))
    )
    (net (code "6") (name "GND") (class "Default")
      (node (ref "C1") (pin "2") (pinfunction "2_2") (pintype "passive"))
      (node (ref "C10") (pin "2") (pinfunction "2_2") (pintype "passive"))
      (node (ref "C15") (pin "2") (pinfunction "2_2") (pintype "passive"))
      (node (ref "C16") (pin "2") (pinfunction "2_2") (pintype "passive"))
      (node (ref "C17") (pin "2") (pinfunction "2_2") (pintype "passive"))
      (node (ref "C18") (pin "2") (pinfunction "2_2") (pintype "passive"))
      (node (ref "C20") (pin "C") (pinfunction "-_C") (pintype "passive"))
      (node (ref "C21") (pin "2") (pinfunction "2_2") (pintype "passive"))
      (node (ref "C23") (pin "1") (pinfunction "1_1") (pintype "passive"))
      (node (ref "C24") (pin "-") (pinfunction "-_-") (pintype "passive"))
      (node (ref "C25") (pin "2") (pinfunction "2_2") (pintype "passive"))
      (node (ref "C3") (pin "1") (pinfunction "1_1") (pintype "passive"))
      (node (ref "C4") (pin "2") (pinfunction "2_2") (pintype "passive"))
      (node (ref "C5") (pin "2") (pinfunction "2_2") (pintype "passive"))
      (node (ref "C6") (pin "1") (pinfunction "1_1") (pintype "passive"))
      (node (ref "C7") (pin "2") (pinfunction "2_2") (pintype "passive"))
      (node (ref "C8") (pin "2") (pinfunction "2_2") (pintype "passive"))
      (node (ref "C9") (pin "2") (pinfunction "2_2") (pintype "passive"))
      (node (ref "D17") (pin "-") (pinfunction "-_-") (pintype "passive"))
      (node (ref "GND") (pin "TP") (pinfunction "PP_TP") (pintype "input"))
      (node (ref "J2") (pin "1") (pinfunction "1_1") (pintype "passive"))
      (node (ref "J6") (pin "1") (pinfunction "5_1") (pintype "passive"))
      (node (ref "PT1") (pin "P$1") (pinfunction "P$1_P$1") (pintype "bidirectional"))
      (node (ref "PT2") (pin "P$1") (pinfunction "P$1_P$1") (pintype "bidirectional"))
      (node (ref "Q3") (pin "1") (pinfunction "G_1") (pintype "passive"))
      (node (ref "Q7") (pin "2") (pinfunction "S_2") (pintype "passive"))
      (node (ref "R31") (pin "1") (pinfunction "1_1") (pintype "passive"))
      (node (ref "R35") (pin "1") (pinfunction "1_1") (pintype "passive"))
      (node (ref "R49") (pin "1") (pinfunction "1_1") (pintype "passive"))
      (node (ref "R50") (pin "1") (pinfunction "1_1") (pintype "passive"))
      (node (ref "R6") (pin "1") (pinfunction "1_1") (pintype "passive"))
      (node (ref "R7") (pin "1") (pinfunction "1_1") (pintype "passive"))
      (node (ref "S2") (pin "1") (pinfunction "1.1_1") (pintype "passive"))
      (node (ref "S2") (pin "2") (pinfunction "1.2_2") (pintype "passive"))
      (node (ref "S3") (pin "1") (pinfunction "1.1_1") (pintype "passive"))
      (node (ref "S3") (pin "2") (pinfunction "1.2_2") (pintype "passive"))
      (node (ref "U1") (pin "3") (pinfunction "VSS_3") (pintype "power_in"))
      (node (ref "U2") (pin "21") (pinfunction "GPIOA_21") (pintype "bidirectional"))
      (node (ref "U2") (pin "22") (pinfunction "VSS_2_22") (pintype "power_in"))
      (node (ref "U2") (pin "23") (pinfunction "VSS_3_23") (pintype "power_in"))
      (node (ref "U2") (pin "25") (pinfunction "VSS_25") (pintype "power_in"))
      (node (ref "U2") (pin "28") (pinfunction "GPIOB_28") (pintype "bidirectional"))
      (node (ref "U2") (pin "30") (pinfunction "SMBA_30") (pintype "input"))
      (node (ref "U2") (pin "6") (pinfunction "VAUX_6") (pintype "input"))
      (node (ref "U2") (pin "8") (pinfunction "~{PRES}_8") (pintype "input"))
      (node (ref "U2") (pin "9") (pinfunction "~{KEYIN}_9") (pintype "input"))
      (node (ref "U3") (pin "21") (pinfunction "AGND_21") (pintype "bidirectional"))
      (node (ref "U3") (pin "3") (pinfunction "GND_3") (pintype "bidirectional"))
      (node (ref "U3") (pin "5") (pinfunction "GND_5") (pintype "bidirectional"))
      (node (ref "U4") (pin "1") (pinfunction "GND_1") (pintype "bidirectional"))
      (node (ref "U5") (pin "1") (pinfunction "GND_1") (pintype "power_in"))
      (node (ref "Y1") (pin "2") (pinfunction "2_2") (pintype "passive"))
      (node (ref "Y2") (pin "2") (pinfunction "2_2") (pintype "passive"))
    )
    (net (code "7") (name "Net-(C11-Pad1)") (class "Default")
      (node (ref "C11") (pin "1") (pinfunction "1_1") (pintype "passive"))
      (node (ref "C12") (pin "2") (pinfunction "2_2") (pintype "passive"))
    )
    (net (code "8") (name "Net-(C13-Pad2)") (class "Default")
      (node (ref "C13") (pin "2") (pinfunction "2_2") (pintype "passive"))
      (node (ref "C14") (pin "1") (pinfunction "1_1") (pintype "passive"))
    )
    (net (code "9") (name "Net-(CHG-PP)") (class "Default")
      (node (ref "CHG") (pin "TP") (pinfunction "PP_TP") (pintype "input"))
      (node (ref "Q3") (pin "2") (pinfunction "S_2") (pintype "passive"))
      (node (ref "U1") (pin "2") (pinfunction "CHG_2") (pintype "output"))
    )
    (net (code "10") (name "Net-(D1-PadC)") (class "Default")
      (node (ref "D1") (pin "C") (pinfunction "C_C") (pintype "passive"))
      (node (ref "R10") (pin "1") (pinfunction "1_1") (pintype "passive"))
      (node (ref "R9") (pin "1") (pinfunction "1_1") (pintype "passive"))
    )
    (net (code "11") (name "Net-(D2-PadA)") (class "Default")
      (node (ref "D2") (pin "A") (pinfunction "A_A") (pintype "passive"))
      (node (ref "R20") (pin "2") (pinfunction "2_2") (pintype "passive"))
      (node (ref "R22") (pin "1") (pinfunction "1_1") (pintype "passive"))
    )
    (net (code "12") (name "Net-(D5-PadC)") (class "Default")
      (node (ref "D5") (pin "C") (pinfunction "C_C") (pintype "passive"))
      (node (ref "R24") (pin "2") (pinfunction "2_2") (pintype "passive"))
    )
    (net (code "13") (name "Net-(D6-Pad+)") (class "Default")
      (node (ref "D6") (pin "+") (pinfunction "+_+") (pintype "passive"))
      (node (ref "R36") (pin "1") (pinfunction "1_1") (pintype "passive"))
    )
    (net (code "14") (name "Net-(D7-Pad+)") (class "Default")
      (node (ref "D7") (pin "+") (pinfunction "+_+") (pintype "passive"))
      (node (ref "R37") (pin "1") (pinfunction "1_1") (pintype "passive"))
    )
    (net (code "15") (name "Net-(D8-Pad+)") (class "Default")
      (node (ref "D8") (pin "+") (pinfunction "+_+") (pintype "passive"))
      (node (ref "R38") (pin "1") (pinfunction "1_1") (pintype "passive"))
    )
    (net (code "16") (name "Net-(D9-Pad+)") (class "Default")
      (node (ref "D9") (pin "+") (pinfunction "+_+") (pintype "passive"))
      (node (ref "R39") (pin "1") (pinfunction "1_1") (pintype "passive"))
    )
    (net (code "17") (name "Net-(D10-Pad+)") (class "Default")
      (node (ref "D10") (pin "+") (pinfunction "+_+") (pintype "passive"))
      (node (ref "R40") (pin "1") (pinfunction "1_1") (pintype "passive"))
    )
    (net (code "18") (name "Net-(D15-Pad+)") (class "Default")
      (node (ref "D15") (pin "+") (pinfunction "+_+") (pintype "passive"))
      (node (ref "R47") (pin "1") (pinfunction "1_1") (pintype "passive"))
    )
    (net (code "19") (name "Net-(D16-Pad+)") (class "Default")
      (node (ref "D16") (pin "+") (pinfunction "+_+") (pintype "passive"))
      (node (ref "R48") (pin "1") (pinfunction "1_1") (pintype "passive"))
    )
    (net (code "20") (name "Net-(D17-Pad+)") (class "Default")
      (node (ref "D17") (pin "+") (pinfunction "+_+") (pintype "passive"))
      (node (ref "R52") (pin "1") (pinfunction "1_1") (pintype "passive"))
    )
    (net (code "21") (name "Net-(DSG-PP)") (class "Default")
      (node (ref "DSG") (pin "TP") (pinfunction "PP_TP") (pintype "input"))
      (node (ref "Q1") (pin "1") (pinfunction "G_1") (pintype "passive"))
      (node (ref "R1") (pin "2") (pinfunction "2_2") (pintype "passive"))
      (node (ref "U1") (pin "1") (pinfunction "DSG_1") (pintype "output"))
    )
    (net (code "22") (name "Net-(J1-Pad1)") (class "Default")
      (node (ref "J1") (pin "1") (pinfunction "1_1") (pintype "passive"))
      (node (ref "J2") (pin "2") (pinfunction "2_2") (pintype "passive"))
    )
    (net (code "23") (name "Net-(J1-Pad3)") (class "Default")
      (node (ref "J1") (pin "3") (pinfunction "3_3") (pintype "passive"))
      (node (ref "R7") (pin "2") (pinfunction "2_2") (pintype "passive"))
    )
    (net (code "24") (name "Net-(J5-Pad1)") (class "Default")
      (node (ref "J5") (pin "1") (pinfunction "1_1") (pintype "passive"))
      (node (ref "R35") (pin "2") (pinfunction "2_2") (pintype "passive"))
    )
    (net (code "25") (name "Net-(J5-Pad3)") (class "Default")
      (node (ref "J5") (pin "3") (pinfunction "3_3") (pintype "passive"))
      (node (ref "R19") (pin "2") (pinfunction "2_2") (pintype "passive"))
    )
    (net (code "26") (name "Net-(J6-2)") (class "Default")
      (node (ref "J6") (pin "4") (pinfunction "2_4") (pintype "passive"))
      (node (ref "U4") (pin "6") (pinfunction "UD-_6") (pintype "bidirectional"))
    )
    (net (code "27") (name "Net-(Q1-D)") (class "Default")
      (node (ref "Q1") (pin "2") (pinfunction "D_2") (pintype "passive"))
      (node (ref "Q2") (pin "2") (pinfunction "D_2") (pintype "passive"))
      (node (ref "R25") (pin "2") (pinfunction "2_2") (pintype "passive"))
    )
    (net (code "28") (name "Net-(Q1-S)") (class "Default")
      (node (ref "C13") (pin "1") (pinfunction "1_1") (pintype "passive"))
      (node (ref "Q1") (pin "3") (pinfunction "S_3") (pintype "passive"))
      (node (ref "R1") (pin "1") (pinfunction "1_1") (pintype "passive"))
      (node (ref "R18") (pin "1") (pinfunction "1_1") (pintype "passive"))
      (node (ref "R2") (pin "1") (pinfunction "1_1") (pintype "passive"))
    )
    (net (code "29") (name "Net-(Q2-G)") (class "Default")
      (node (ref "D2") (pin "C") (pinfunction "C_C") (pintype "passive"))
      (node (ref "Q2") (pin "1") (pinfunction "G_1") (pintype "passive"))
      (node (ref "R20") (pin "1") (pinfunction "1_1") (pintype "passive"))
      (node (ref "R21") (pin "2") (pinfunction "2_2") (pintype "passive"))
    )
    (net (code "30") (name "Net-(Q3-D)") (class "Default")
      (node (ref "Q3") (pin "3") (pinfunction "D_3") (pintype "passive"))
      (node (ref "R22") (pin "2") (pinfunction "2_2") (pintype "passive"))
    )
    (net (code "31") (name "Net-(Q4-D)") (class "Default")
      (node (ref "Q4") (pin "3") (pinfunction "D_3") (pintype "passive"))
      (node (ref "R25") (pin "1") (pinfunction "1_1") (pintype "passive"))
    )
    (net (code "32") (name "Net-(Q4-G)") (class "Default")
      (node (ref "Q4") (pin "1") (pinfunction "G_1") (pintype "passive"))
      (node (ref "R23") (pin "2") (pinfunction "2_2") (pintype "passive"))
      (node (ref "R24") (pin "1") (pinfunction "1_1") (pintype "passive"))
    )
    (net (code "33") (name "Net-(Q5-B)") (class "Default")
      (node (ref "Q5") (pin "1") (pinfunction "B_1") (pintype "passive"))
      (node (ref "R26") (pin "1") (pinfunction "1_1") (pintype "passive"))
    )
    (net (code "34") (name "Net-(Q5-C)") (class "Default")
      (node (ref "D5") (pin "A") (pinfunction "A_A") (pintype "passive"))
      (node (ref "Q5") (pin "3") (pinfunction "C_3") (pintype "passive"))
    )
    (net (code "35") (name "Net-(Q6-D)") (class "Default")
      (node (ref "Q6") (pin "3") (pinfunction "D_3") (pintype "passive"))
      (node (ref "R30") (pin "2") (pinfunction "2_2") (pintype "passive"))
    )
    (net (code "36") (name "Net-(Q6-G)") (class "Default")
      (node (ref "Q6") (pin "1") (pinfunction "G_1") (pintype "passive"))
      (node (ref "R28") (pin "2") (pinfunction "2_2") (pintype "passive"))
      (node (ref "R29") (pin "1") (pinfunction "1_1") (pintype "passive"))
    )
    (net (code "37") (name "Net-(Q7-D)") (class "Default")
      (node (ref "Q7") (pin "3") (pinfunction "D_3") (pintype "passive"))
      (node (ref "R28") (pin "1") (pinfunction "1_1") (pintype "passive"))
    )
    (net (code "38") (name "Net-(Q7-G)") (class "Default")
      (node (ref "Q7") (pin "1") (pinfunction "G_1") (pintype "passive"))
      (node (ref "R27") (pin "1") (pinfunction "1_1") (pintype "passive"))
      (node (ref "U2") (pin "12") (pinfunction "VEN_12") (pintype "output"))
    )
    (net (code "39") (name "Net-(Q8-D)") (class "Default")
      (node (ref "Q8") (pin "3") (pinfunction "D_3") (pintype "passive"))
      (node (ref "R15") (pin "1") (pinfunction "1_1") (pintype "passive"))
    )
    (net (code "40") (name "Net-(Q8-G)") (class "Default")
      (node (ref "C8") (pin "1") (pinfunction "1_1") (pintype "passive"))
      (node (ref "D11") (pin "C") (pinfunction "C_C") (pintype "passive"))
      (node (ref "Q8") (pin "1") (pinfunction "G_1") (pintype "passive"))
      (node (ref "R12") (pin "2") (pinfunction "2_2") (pintype "passive"))
      (node (ref "U1") (pin "13") (pinfunction "VC4_13") (pintype "input"))
      (node (ref "U1") (pin "14") (pinfunction "VC3_14") (pintype "input"))
      (node (ref "U1") (pin "15") (pinfunction "VC2_15") (pintype "input"))
    )
    (net (code "41") (name "Net-(Q8-S)") (class "Default")
      (node (ref "D11") (pin "A") (pinfunction "A_A") (pintype "passive"))
      (node (ref "Q8") (pin "2") (pinfunction "S_2") (pintype "passive"))
      (node (ref "R12") (pin "1") (pinfunction "1_1") (pintype "passive"))
      (node (ref "R16") (pin "2") (pinfunction "2_2") (pintype "passive"))
      (node (ref "X1") (pin "3") (pinfunction "S_3") (pintype "passive"))
    )
    (net (code "42") (name "Net-(Q9-D)") (class "Default")
      (node (ref "Q9") (pin "3") (pinfunction "D_3") (pintype "passive"))
      (node (ref "R16") (pin "1") (pinfunction "1_1") (pintype "passive"))
    )
    (net (code "43") (name "Net-(Q9-G)") (class "Default")
      (node (ref "C9") (pin "1") (pinfunction "1_1") (pintype "passive"))
      (node (ref "D12") (pin "C") (pinfunction "C_C") (pintype "passive"))
      (node (ref "Q9") (pin "1") (pinfunction "G_1") (pintype "passive"))
      (node (ref "R13") (pin "2") (pinfunction "2_2") (pintype "passive"))
      (node (ref "U1") (pin "16") (pinfunction "VC1_16") (pintype "input"))
    )
    (net (code "44") (name "Net-(Q10-D)") (class "Default")
      (node (ref "Q10") (pin "3") (pinfunction "D_3") (pintype "passive"))
      (node (ref "R17") (pin "1") (pinfunction "1_1") (pintype "passive"))
    )
    (net (code "45") (name "Net-(Q10-G)") (class "Default")
      (node (ref "C10") (pin "1") (pinfunction "1_1") (pintype "passive"))
      (node (ref "D13") (pin "C") (pinfunction "C_C") (pintype "passive"))
      (node (ref "Q10") (pin "1") (pinfunction "G_1") (pintype "passive"))
      (node (ref "R14") (pin "2") (pinfunction "2_2") (pintype "passive"))
      (node (ref "U1") (pin "17") (pinfunction "VC0_17") (pintype "input"))
    )
    (net (code "46") (name "Net-(Q10-S)") (class "Default")
      (node (ref "D13") (pin "A") (pinfunction "A_A") (pintype "passive"))
      (node (ref "Q10") (pin "2") (pinfunction "S_2") (pintype "passive"))
      (node (ref "R14") (pin "1") (pinfunction "1_1") (pintype "passive"))
      (node (ref "X1") (pin "1") (pinfunction "S_1") (pintype "passive"))
    )
    (net (code "47") (name "Net-(Q13-D)") (class "Default")
      (node (ref "D12") (pin "A") (pinfunction "A_A") (pintype "passive"))
      (node (ref "Q13") (pin "3") (pinfunction "D_3") (pintype "passive"))
      (node (ref "Q9") (pin "2") (pinfunction "S_2") (pintype "passive"))
      (node (ref "R13") (pin "1") (pinfunction "1_1") (pintype "passive"))
      (node (ref "R17") (pin "2") (pinfunction "2_2") (pintype "passive"))
      (node (ref "S1") (pin "1") (pinfunction "1.1_1") (pintype "passive"))
      (node (ref "S1") (pin "2") (pinfunction "1.2_2") (pintype "passive"))
      (node (ref "X1") (pin "2") (pinfunction "S_2") (pintype "passive"))
    )
    (net (code "48") (name "Net-(Q13-S)") (class "Default")
      (node (ref "Q13") (pin "2") (pinfunction "S_2") (pintype "passive"))
      (node (ref "R8") (pin "2") (pinfunction "2_2") (pintype "passive"))
      (node (ref "S1") (pin "3") (pinfunction "2.1_3") (pintype "passive"))
      (node (ref "S1") (pin "4") (pinfunction "2.2_4") (pintype "passive"))
    )
    (net (code "49") (name "Net-(S2-2.1)") (class "Default")
      (node (ref "R33") (pin "1") (pinfunction "1_1") (pintype "passive"))
      (node (ref "S2") (pin "3") (pinfunction "2.1_3") (pintype "passive"))
      (node (ref "S2") (pin "4") (pinfunction "2.2_4") (pintype "passive"))
      (node (ref "U2") (pin "14") (pinfunction "~{DISP}_14") (pintype "input"))
    )
    (net (code "50") (name "Net-(S3-2.1)") (class "Default")
      (node (ref "C22") (pin "2") (pinfunction "2_2") (pintype "passive"))
      (node (ref "R34") (pin "1") (pinfunction "1_1") (pintype "passive"))
      (node (ref "S3") (pin "3") (pinfunction "2.1_3") (pintype "passive"))
      (node (ref "S3") (pin "4") (pinfunction "2.2_4") (pintype "passive"))
      (node (ref "U3") (pin "29") (pinfunction "PC6(/RESET)_29") (pintype "bidirectional"))
    )
    (net (code "51") (name "Net-(U1-BAT)") (class "Default")
      (node (ref "C6") (pin "2") (pinfunction "2_2") (pintype "passive"))
      (node (ref "R9") (pin "2") (pinfunction "2_2") (pintype "passive"))
      (node (ref "U1") (pin "10") (pinfunction "BAT_10") (pintype "power_in"))
      (node (ref "U1") (pin "9") (pinfunction "REGSRC_9") (pintype "input"))
    )
    (net (code "52") (name "Net-(U1-CAP1)") (class "Default")
      (node (ref "C4") (pin "1") (pinfunction "1_1") (pintype "passive"))
      (node (ref "U1") (pin "7") (pinfunction "CAP1_7") (pintype "output"))
    )
    (net (code "53") (name "Net-(U1-SRN)") (class "Default")
      (node (ref "C1") (pin "1") (pinfunction "1_1") (pintype "passive"))
      (node (ref "C2") (pin "2") (pinfunction "2_2") (pintype "passive"))
      (node (ref "R2") (pin "2") (pinfunction "2_2") (pintype "passive"))
      (node (ref "U1") (pin "19") (pinfunction "SRN_19") (pintype "input"))
    )
    (net (code "54") (name "Net-(U1-SRP)") (class "Default")
      (node (ref "C2") (pin "1") (pinfunction "1_1") (pintype "passive"))
      (node (ref "C3") (pin "2") (pinfunction "2_2") (pintype "passive"))
      (node (ref "R3") (pin "2") (pinfunction "2_2") (pintype "passive"))
      (node (ref "U1") (pin "18") (pinfunction "SRP_18") (pintype "input"))
    )
    (net (code "55") (name "Net-(U1-TS1)") (class "Default")
      (node (ref "C25") (pin "1") (pinfunction "1_1") (pintype "passive"))
      (node (ref "J1") (pin "2") (pinfunction "2_2") (pintype "passive"))
      (node (ref "R8") (pin "1") (pinfunction "1_1") (pintype "passive"))
      (node (ref "U1") (pin "6") (pinfunction "TS1_6") (pintype "input"))
    )
    (net (code "56") (name "Net-(U1-VC5)") (class "Default")
      (node (ref "C7") (pin "1") (pinfunction "1_1") (pintype "passive"))
      (node (ref "R11") (pin "2") (pinfunction "2_2") (pintype "passive"))
      (node (ref "U1") (pin "12") (pinfunction "VC5_12") (pintype "input"))
    )
    (net (code "57") (name "Net-(U2A-BAT)") (class "Default")
      (node (ref "C16") (pin "1") (pinfunction "1_1") (pintype "passive"))
      (node (ref "R30") (pin "1") (pinfunction "1_1") (pintype "passive"))
      (node (ref "R31") (pin "2") (pinfunction "2_2") (pintype "passive"))
      (node (ref "U2") (pin "7") (pinfunction "BAT_7") (pintype "input"))
    )
    (net (code "58") (name "Net-(U2A-LED1)") (class "Default")
      (node (ref "D6") (pin "-") (pinfunction "-_-") (pintype "passive"))
      (node (ref "U2") (pin "16") (pinfunction "LED1_16") (pintype "output"))
    )
    (net (code "59") (name "Net-(U2A-LED2)") (class "Default")
      (node (ref "D7") (pin "-") (pinfunction "-_-") (pintype "passive"))
      (node (ref "U2") (pin "17") (pinfunction "LED2_17") (pintype "output"))
    )
    (net (code "60") (name "Net-(U2A-LED3)") (class "Default")
      (node (ref "D8") (pin "-") (pinfunction "-_-") (pintype "passive"))
      (node (ref "U2") (pin "18") (pinfunction "LED3_18") (pintype "output"))
    )
    (net (code "61") (name "Net-(U2A-LED4)") (class "Default")
      (node (ref "D9") (pin "-") (pinfunction "-_-") (pintype "passive"))
      (node (ref "U2") (pin "19") (pinfunction "LED4_19") (pintype "output"))
    )
    (net (code "62") (name "Net-(U2A-LED5)") (class "Default")
      (node (ref "D10") (pin "-") (pinfunction "-_-") (pintype "passive"))
      (node (ref "U2") (pin "20") (pinfunction "LED5_20") (pintype "output"))
    )
    (net (code "63") (name "Net-(U2A-RBI)") (class "Default")
      (node (ref "C15") (pin "1") (pinfunction "1_1") (pintype "passive"))
      (node (ref "U2") (pin "27") (pinfunction "RBI_27") (pintype "input"))
    )
    (net (code "64") (name "Net-(U2A-~{MRST})") (class "Default")
      (node (ref "R32") (pin "1") (pinfunction "1_1") (pintype "passive"))
      (node (ref "U2") (pin "24") (pinfunction "~{MRST}_24") (pintype "input"))
    )
    (net (code "65") (name "Net-(U3-AREF)") (class "Default")
      (node (ref "C23") (pin "2") (pinfunction "2_2") (pintype "passive"))
      (node (ref "U3") (pin "20") (pinfunction "AREF_20") (pintype "bidirectional"))
    )
    (net (code "66") (name "Net-(U3-PB6(XTAL1{slash}TOSC1))") (class "Default")
      (node (ref "U3") (pin "7") (pinfunction "PB6(XTAL1/TOSC1)_7") (pintype "bidirectional"))
      (node (ref "Y2") (pin "1") (pinfunction "1_1") (pintype "passive"))
    )
    (net (code "67") (name "Net-(U3-PB7(XTAL2{slash}TOSC2))") (class "Default")
      (node (ref "U3") (pin "8") (pinfunction "PB7(XTAL2/TOSC2)_8") (pintype "bidirectional"))
      (node (ref "Y2") (pin "3") (pinfunction "3_3") (pintype "passive"))
    )
    (net (code "68") (name "Net-(U3-PD0(RXD))") (class "Default")
      (node (ref "D16") (pin "-") (pinfunction "-_-") (pintype "passive"))
      (node (ref "R46") (pin "2") (pinfunction "2_2") (pintype "passive"))
      (node (ref "U3") (pin "30") (pinfunction "PD0(RXD)_30") (pintype "bidirectional"))
    )
    (net (code "69") (name "Net-(U3-PD1(TXD))") (class "Default")
      (node (ref "D15") (pin "-") (pinfunction "-_-") (pintype "passive"))
      (node (ref "R45") (pin "2") (pinfunction "2_2") (pintype "passive"))
      (node (ref "U3") (pin "31") (pinfunction "PD1(TXD)_31") (pintype "bidirectional"))
    )
    (net (code "70") (name "Net-(U3-PD5(T1))") (class "Default")
      (node (ref "R52") (pin "2") (pinfunction "2_2") (pintype "passive"))
      (node (ref "U3") (pin "9") (pinfunction "PD5(T1)_9") (pintype "bidirectional"))
    )
    (net (code "71") (name "Net-(U4-RXD)") (class "Default")
      (node (ref "R45") (pin "1") (pinfunction "1_1") (pintype "passive"))
      (node (ref "U4") (pin "3") (pinfunction "RXD_3") (pintype "bidirectional"))
    )
    (net (code "72") (name "Net-(U4-TXD)") (class "Default")
      (node (ref "R46") (pin "1") (pinfunction "1_1") (pintype "passive"))
      (node (ref "U4") (pin "2") (pinfunction "TXD_2") (pintype "bidirectional"))
    )
    (net (code "73") (name "Net-(U4-UD+)") (class "Default")
      (node (ref "J6") (pin "3") (pinfunction "3_3") (pintype "passive"))
      (node (ref "U4") (pin "5") (pinfunction "UD+_5") (pintype "bidirectional"))
    )
    (net (code "74") (name "Net-(U4-XI)") (class "Default")
      (node (ref "U4") (pin "7") (pinfunction "XI_7") (pintype "bidirectional"))
      (node (ref "Y1") (pin "1") (pinfunction "1_1") (pintype "passive"))
    )
    (net (code "75") (name "Net-(U4-XO)") (class "Default")
      (node (ref "U4") (pin "8") (pinfunction "XO_8") (pintype "bidirectional"))
      (node (ref "Y1") (pin "3") (pinfunction "3_3") (pintype "passive"))
    )
    (net (code "76") (name "Net-(U4-~{DTR})") (class "Default")
      (node (ref "C22") (pin "1") (pinfunction "1_1") (pintype "passive"))
      (node (ref "U4") (pin "13") (pinfunction "~{DTR}_13") (pintype "bidirectional"))
    )
    (net (code "77") (name "Net-(U5-SW)") (class "Default")
      (node (ref "C19") (pin "2") (pinfunction "2_2") (pintype "passive"))
      (node (ref "L1") (pin "2") (pinfunction "2_2") (pintype "passive"))
      (node (ref "U5") (pin "2") (pinfunction "SW_2") (pintype "passive"))
    )
    (net (code "78") (name "Net-(U5-VBST)") (class "Default")
      (node (ref "C19") (pin "1") (pinfunction "1_1") (pintype "passive"))
      (node (ref "U5") (pin "6") (pinfunction "VBST_6") (pintype "input"))
    )
    (net (code "79") (name "Net-(U5-VFB)") (class "Default")
      (node (ref "R50") (pin "2") (pinfunction "2_2") (pintype "passive"))
      (node (ref "R51") (pin "1") (pinfunction "1_1") (pintype "passive"))
      (node (ref "U5") (pin "4") (pinfunction "VFB_4") (pintype "input"))
    )
    (net (code "80") (name "PACK-") (class "Default")
      (node (ref "C11") (pin "2") (pinfunction "2_2") (pintype "passive"))
      (node (ref "C14") (pin "2") (pinfunction "2_2") (pintype "passive"))
      (node (ref "D4") (pin "A") (pinfunction "A_A") (pintype "passive"))
      (node (ref "J3") (pin "-") (pinfunction "-_-") (pintype "passive"))
      (node (ref "Q2") (pin "3") (pinfunction "S_3") (pintype "passive"))
      (node (ref "Q4") (pin "2") (pinfunction "S_2") (pintype "passive"))
      (node (ref "R21") (pin "1") (pinfunction "1_1") (pintype "passive"))
      (node (ref "R23") (pin "1") (pinfunction "1_1") (pintype "passive"))
    )
    (net (code "81") (name "PRECHG") (class "Default")
      (node (ref "R26") (pin "2") (pinfunction "2_2") (pintype "passive"))
      (node (ref "U2") (pin "5") (pinfunction "~{PRECHG}_5") (pintype "output"))
    )
    (net (code "82") (name "REGOUT") (class "Default")
      (node (ref "C17") (pin "1") (pinfunction "1_1") (pintype "passive"))
      (node (ref "C5") (pin "1") (pinfunction "1_1") (pintype "passive"))
      (node (ref "Q11") (pin "1") (pinfunction "G_1") (pintype "passive"))
      (node (ref "Q12") (pin "1") (pinfunction "G_1") (pintype "passive"))
      (node (ref "Q5") (pin "2") (pinfunction "E_2") (pintype "passive"))
      (node (ref "R27") (pin "2") (pinfunction "2_2") (pintype "passive"))
      (node (ref "R32") (pin "2") (pinfunction "2_2") (pintype "passive"))
      (node (ref "R33") (pin "2") (pinfunction "2_2") (pintype "passive"))
      (node (ref "R36") (pin "2") (pinfunction "2_2") (pintype "passive"))
      (node (ref "R37") (pin "2") (pinfunction "2_2") (pintype "passive"))
      (node (ref "R38") (pin "2") (pinfunction "2_2") (pintype "passive"))
      (node (ref "R39") (pin "2") (pinfunction "2_2") (pintype "passive"))
      (node (ref "R4") (pin "2") (pinfunction "2_2") (pintype "passive"))
      (node (ref "R40") (pin "2") (pinfunction "2_2") (pintype "passive"))
      (node (ref "R41") (pin "2") (pinfunction "2_2") (pintype "passive"))
      (node (ref "R43") (pin "2") (pinfunction "2_2") (pintype "passive"))
      (node (ref "R5") (pin "2") (pinfunction "2_2") (pintype "passive"))
      (node (ref "REGOUT") (pin "TP") (pinfunction "PP_TP") (pintype "input"))
      (node (ref "U1") (pin "8") (pinfunction "REGOUT_8") (pintype "power_in"))
      (node (ref "U2") (pin "26") (pinfunction "VCC_26") (pintype "power_in"))
    )
    (net (code "83") (name "SCL") (class "Default")
      (node (ref "R5") (pin "1") (pinfunction "1_1") (pintype "passive"))
      (node (ref "SCL") (pin "TP") (pinfunction "PP_TP") (pintype "input"))
      (node (ref "U1") (pin "5") (pinfunction "SCL_5") (pintype "input"))
      (node (ref "U2") (pin "4") (pinfunction "SCL_4") (pintype "bidirectional"))
    )
    (net (code "84") (name "SDA") (class "Default")
      (node (ref "R4") (pin "1") (pinfunction "1_1") (pintype "passive"))
      (node (ref "SDA") (pin "TP") (pinfunction "PP_TP") (pintype "input"))
      (node (ref "U1") (pin "4") (pinfunction "SDA_4") (pintype "bidirectional"))
      (node (ref "U2") (pin "3") (pinfunction "SDA_3") (pintype "bidirectional"))
    )
    (net (code "85") (name "SMBC") (class "Default")
      (node (ref "Q11") (pin "2") (pinfunction "S_2") (pintype "passive"))
      (node (ref "R43") (pin "1") (pinfunction "1_1") (pintype "passive"))
      (node (ref "SMBC") (pin "TP") (pinfunction "PP_TP") (pintype "input"))
      (node (ref "U2") (pin "13") (pinfunction "SMBC_13") (pintype "bidirectional"))
    )
    (net (code "86") (name "SMBC_MCU") (class "Default")
      (node (ref "Q11") (pin "3") (pinfunction "D_3") (pintype "passive"))
      (node (ref "R44") (pin "1") (pinfunction "1_1") (pintype "passive"))
      (node (ref "SMBC_MCU") (pin "TP") (pinfunction "PP_TP") (pintype "input"))
      (node (ref "U3") (pin "28") (pinfunction "PC5(ADC5/SCL)_28") (pintype "bidirectional"))
    )
    (net (code "87") (name "SMBD") (class "Default")
      (node (ref "Q12") (pin "2") (pinfunction "S_2") (pintype "passive"))
      (node (ref "R41") (pin "1") (pinfunction "1_1") (pintype "passive"))
      (node (ref "SMBD") (pin "TP") (pinfunction "PP_TP") (pintype "input"))
      (node (ref "U2") (pin "11") (pinfunction "SMBD_11") (pintype "bidirectional"))
    )
    (net (code "88") (name "SMBD_MCU") (class "Default")
      (node (ref "Q12") (pin "3") (pinfunction "D_3") (pintype "passive"))
      (node (ref "R42") (pin "1") (pinfunction "1_1") (pintype "passive"))
      (node (ref "SMBD_MCU") (pin "TP") (pinfunction "PP_TP") (pintype "input"))
      (node (ref "U3") (pin "27") (pinfunction "PC4(ADC4/SDA)_27") (pintype "bidirectional"))
    )
    (net (code "89") (name "TS-SELECT") (class "Default")
      (node (ref "J5") (pin "2") (pinfunction "2_2") (pintype "passive"))
      (node (ref "U3") (pin "24") (pinfunction "PC1(ADC1)_24") (pintype "bidirectional"))
    )
    (net (code "90") (name "USB+") (class "Default")
      (node (ref "C20") (pin "A") (pinfunction "+_A") (pintype "passive"))
      (node (ref "C21") (pin "1") (pinfunction "1_1") (pintype "passive"))
      (node (ref "D14") (pin "A") (pinfunction "A_A") (pintype "passive"))
      (node (ref "J6") (pin "5") (pinfunction "1_5") (pintype "passive"))
      (node (ref "R47") (pin "2") (pinfunction "2_2") (pintype "passive"))
      (node (ref "R48") (pin "2") (pinfunction "2_2") (pintype "passive"))
      (node (ref "U4") (pin "16") (pinfunction "VCC_16") (pintype "bidirectional"))
    )
    (net (code "91") (name "unconnected-(J6-4-Pad2)") (class "Default")
      (node (ref "J6") (pin "2") (pinfunction "4_2") (pintype "passive"))
    )
    (net (code "92") (name "unconnected-(S1-SH-Pad5)") (class "Default")
      (node (ref "S1") (pin "5") (pinfunction "SH_5") (pintype "passive"))
    )
    (net (code "93") (name "unconnected-(S2-SH-Pad5)") (class "Default")
      (node (ref "S2") (pin "5") (pinfunction "SH_5") (pintype "passive"))
    )
    (net (code "94") (name "unconnected-(S3-SH-Pad5)") (class "Default")
      (node (ref "S3") (pin "5") (pinfunction "SH_5") (pintype "passive"))
    )
    (net (code "95") (name "unconnected-(U1-NC-Pad11)") (class "Default")
      (node (ref "U1") (pin "11") (pinfunction "NC_11") (pintype "no_connect"))
    )
    (net (code "96") (name "unconnected-(U2A-ADREN-Pad29)") (class "Default")
      (node (ref "U2") (pin "29") (pinfunction "ADREN_29") (pintype "output"))
    )
    (net (code "97") (name "unconnected-(U2A-COM-Pad1)") (class "Default")
      (node (ref "U2") (pin "1") (pinfunction "COM_1") (pintype "output"))
    )
    (net (code "98") (name "unconnected-(U2A-PWRM-Pad15)") (class "Default")
      (node (ref "U2") (pin "15") (pinfunction "PWRM_15") (pintype "output"))
    )
    (net (code "99") (name "unconnected-(U2A-SAFE-Pad10)") (class "Default")
      (node (ref "U2") (pin "10") (pinfunction "SAFE_10") (pintype "output"))
    )
    (net (code "100") (name "unconnected-(U3-ADC6-Pad19)") (class "Default")
      (node (ref "U3") (pin "19") (pinfunction "ADC6_19") (pintype "bidirectional"))
    )
    (net (code "101") (name "unconnected-(U3-ADC7-Pad22)") (class "Default")
      (node (ref "U3") (pin "22") (pinfunction "ADC7_22") (pintype "bidirectional"))
    )
    (net (code "102") (name "unconnected-(U3-PB0(ICP)-Pad12)") (class "Default")
      (node (ref "U3") (pin "12") (pinfunction "PB0(ICP)_12") (pintype "bidirectional"))
    )
    (net (code "103") (name "unconnected-(U3-PB1(OC1A)-Pad13)") (class "Default")
      (node (ref "U3") (pin "13") (pinfunction "PB1(OC1A)_13") (pintype "bidirectional"))
    )
    (net (code "104") (name "unconnected-(U3-PB2(SS{slash}OC1B)-Pad14)") (class "Default")
      (node (ref "U3") (pin "14") (pinfunction "PB2(SS/OC1B)_14") (pintype "bidirectional"))
    )
    (net (code "105") (name "unconnected-(U3-PB3(MOSI{slash}OC2)-Pad15)") (class "Default")
      (node (ref "U3") (pin "15") (pinfunction "PB3(MOSI/OC2)_15") (pintype "bidirectional"))
    )
    (net (code "106") (name "unconnected-(U3-PB4(MISO)-Pad16)") (class "Default")
      (node (ref "U3") (pin "16") (pinfunction "PB4(MISO)_16") (pintype "bidirectional"))
    )
    (net (code "107") (name "unconnected-(U3-PB5(SCK)-Pad17)") (class "Default")
      (node (ref "U3") (pin "17") (pinfunction "PB5(SCK)_17") (pintype "bidirectional"))
    )
    (net (code "108") (name "unconnected-(U3-PC0(ADC0)-Pad23)") (class "Default")
      (node (ref "U3") (pin "23") (pinfunction "PC0(ADC0)_23") (pintype "bidirectional"))
    )
    (net (code "109") (name "unconnected-(U3-PC2(ADC2)-Pad25)") (class "Default")
      (node (ref "U3") (pin "25") (pinfunction "PC2(ADC2)_25") (pintype "bidirectional"))
    )
    (net (code "110") (name "unconnected-(U3-PC3(ADC3)-Pad26)") (class "Default")
      (node (ref "U3") (pin "26") (pinfunction "PC3(ADC3)_26") (pintype "bidirectional"))
    )
    (net (code "111") (name "unconnected-(U3-PD2(INT0)-Pad32)") (class "Default")
      (node (ref "U3") (pin "32") (pinfunction "PD2(INT0)_32") (pintype "bidirectional"))
    )
    (net (code "112") (name "unconnected-(U3-PD4(XCK{slash}T0)-Pad2)") (class "Default")
      (node (ref "U3") (pin "2") (pinfunction "PD4(XCK/T0)_2") (pintype "bidirectional"))
    )
    (net (code "113") (name "unconnected-(U3-PD6(AIN0)-Pad10)") (class "Default")
      (node (ref "U3") (pin "10") (pinfunction "PD6(AIN0)_10") (pintype "bidirectional"))
    )
    (net (code "114") (name "unconnected-(U3-PD7(AIN1)-Pad11)") (class "Default")
      (node (ref "U3") (pin "11") (pinfunction "PD7(AIN1)_11") (pintype "bidirectional"))
    )
    (net (code "115") (name "unconnected-(U4-R232-Pad15)") (class "Default")
      (node (ref "U4") (pin "15") (pinfunction "R232_15") (pintype "bidirectional"))
    )
    (net (code "116") (name "unconnected-(U4-V3-Pad4)") (class "Default")
      (node (ref "U4") (pin "4") (pinfunction "V3_4") (pintype "bidirectional"))
    )
    (net (code "117") (name "unconnected-(U4-~{CTS}-Pad9)") (class "Default")
      (node (ref "U4") (pin "9") (pinfunction "~{CTS}_9") (pintype "bidirectional"))
    )
    (net (code "118") (name "unconnected-(U4-~{DCD}-Pad12)") (class "Default")
      (node (ref "U4") (pin "12") (pinfunction "~{DCD}_12") (pintype "bidirectional"))
    )
    (net (code "119") (name "unconnected-(U4-~{DSR}-Pad10)") (class "Default")
      (node (ref "U4") (pin "10") (pinfunction "~{DSR}_10") (pintype "bidirectional"))
    )
    (net (code "120") (name "unconnected-(U4-~{RI}-Pad11)") (class "Default")
      (node (ref "U4") (pin "11") (pinfunction "~{RI}_11") (pintype "bidirectional"))
    )
    (net (code "121") (name "unconnected-(U4-~{RTS}-Pad14)") (class "Default")
      (node (ref "U4") (pin "14") (pinfunction "~{RTS}_14") (pintype "bidirectional"))
    )
  )
)
